# fonte.net
KiCad netlist of a schematic drawn in Altium Designer
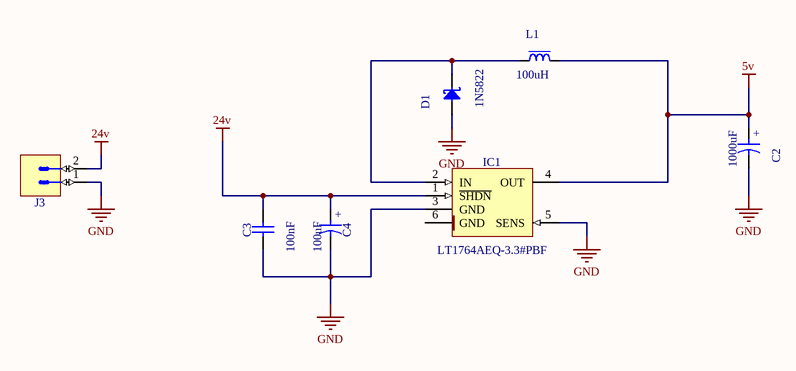
[diagram p0: fonte.SchDoc]

(export (version "E")
  (design (tool "Eeschema 10.0.6"))
  (components
    (comp (ref "C2")
      (value "1000uF")
      (footprint "CAPPR500-1350X2200")
      (description "Polarised capacitor")
      (fields
        (field (name "PART NUMBER") "CAER_1000UF_35V_20%_VISHAY_MAL203850102E3")
        (field (name "VOLTAGE") "35V")
        (field (name "AUTHOR") "CERN DEM JLC")
      )
      (libsource (lib "Capacitors") (part "Capacitor - polarized"))
    )
    (comp (ref "C3")
      (value "100nF")
      (footprint "CAPC2012X135N")
      (description "Non-polarised capacitor")
      (fields
        (field (name "PART NUMBER") "CC0805_100NF_50V_10%_X7R")
        (field (name "VOLTAGE") "50V")
        (field (name "AUTHOR") "CERN DEM JLC")
      )
      (libsource (lib "Capacitors") (part "Capacitor - non polarized"))
    )
    (comp (ref "C4")
      (value "100uF")
      (footprint "CAPPR500-1050X1750")
      (description "Polarised capacitor")
      (fields
        (field (name "PART NUMBER") "CAER_100UF_63V_20%_500-1050X1750_LESR0R190")
        (field (name "VOLTAGE") "63V")
        (field (name "AUTHOR") "CERN DEM JLC")
      )
      (libsource (lib "Capacitors") (part "Capacitor - polarized"))
    )
    (comp (ref "D1")
      (value "1N5822")
      (footprint "DO-201AD")
      (description "Schottky Diode")
      (fields
        (field (name "VOLTAGE") "40V")
        (field (name "POWER") "3A")
        (field (name "AUTHOR") "CERN DEM JLC")
      )
      (libsource (lib "ICs And Semiconductors") (part "Diode Schottky"))
    )
    (comp (ref "IC1")
      (value "LT1764AEQ-3.3#PBF")
      (footprint "TO170P1394X457-6N-R900X1060")
      (description "3A, Fast Transient Response, Low Noise, LDO Regulators")
      (fields (field (name "MANUFACTURER") "LINEAR TECHNOLOGY") (field (name "AUTHOR") "CERN DEM JLC"))
      (libsource (lib "ICs And Semiconductors") (part "LT1764AEQ-X.X"))
    )
    (comp (ref "J3")
      (value "~")
      (footprint "PHOENIX_1757242")
      (description "Connector 2 Male")
      (fields
        (field (name "PART NUMBER") "PHOENIX_1757242")
        (field (name "MANUFACTURER") "PHOENIX CONTACT")
        (field (name "AUTHOR") "CERN DEM JLC")
      )
      (libsource (lib "Connectors") (part "Connector 2 Male"))
    )
    (comp (ref "L1")
      (value "100uH")
      (footprint "IND_WURTH_WE-PD4_L")
      (description "Inductor With Magnetic core")
      (fields
        (field (name "PART NUMBER") "IND_3.3UH_20%_WURTH_WE-PD4_74456033")
        (field (name "POWER") "5.3A")
        (field (name "AUTHOR") "CERN DEM JLC")
      )
      (libsource (lib "Inductors & Transformers") (part "Inductor With Magnetic core"))
    )
  )
  (nets
    (net (code "1") (name "5v") (class "Default")
      (node (ref "C2") (pin "1") (pinfunction "1_1") (pintype "passive"))
      (node (ref "IC1") (pin "4") (pinfunction "OUT_4") (pintype "power_in"))
      (node (ref "L1") (pin "2") (pinfunction "2_2") (pintype "passive"))
    )
    (net (code "2") (name "24v") (class "Default")
      (node (ref "C3") (pin "2") (pinfunction "2_2") (pintype "passive"))
      (node (ref "C4") (pin "1") (pinfunction "1_1") (pintype "passive"))
      (node (ref "IC1") (pin "1") (pinfunction "~{SHDN}_1") (pintype "input"))
      (node (ref "J3") (pin "2") (pinfunction "2_2") (pintype "bidirectional"))
    )
    (net (code "3") (name "GND") (class "Default")
      (node (ref "C2") (pin "2") (pinfunction "2_2") (pintype "passive"))
      (node (ref "C3") (pin "1") (pinfunction "1_1") (pintype "passive"))
      (node (ref "C4") (pin "2") (pinfunction "2_2") (pintype "passive"))
      (node (ref "D1") (pin "2") (pinfunction "A_2") (pintype "passive"))
      (node (ref "IC1") (pin "3") (pinfunction "GND_3") (pintype "power_in"))
      (node (ref "IC1") (pin "5") (pinfunction "SENS_5") (pintype "input"))
      (node (ref "J3") (pin "1") (pinfunction "1_1") (pintype "bidirectional"))
    )
    (net (code "4") (name "Net-(D1-C)") (class "Default")
      (node (ref "D1") (pin "1") (pinfunction "C_1") (pintype "passive"))
      (node (ref "IC1") (pin "2") (pinfunction "IN_2") (pintype "input"))
      (node (ref "L1") (pin "1") (pinfunction "1_1") (pintype "passive"))
    )
    (net (code "5") (name "unconnected-(IC1-GND-Pad6)") (class "Default")
      (node (ref "IC1") (pin "6") (pinfunction "GND_6") (pintype "power_in"))
    )
  )
)
